# isolated_dcdc_5to3_3.net
KiCad netlist of a schematic drawn in Altium Designer
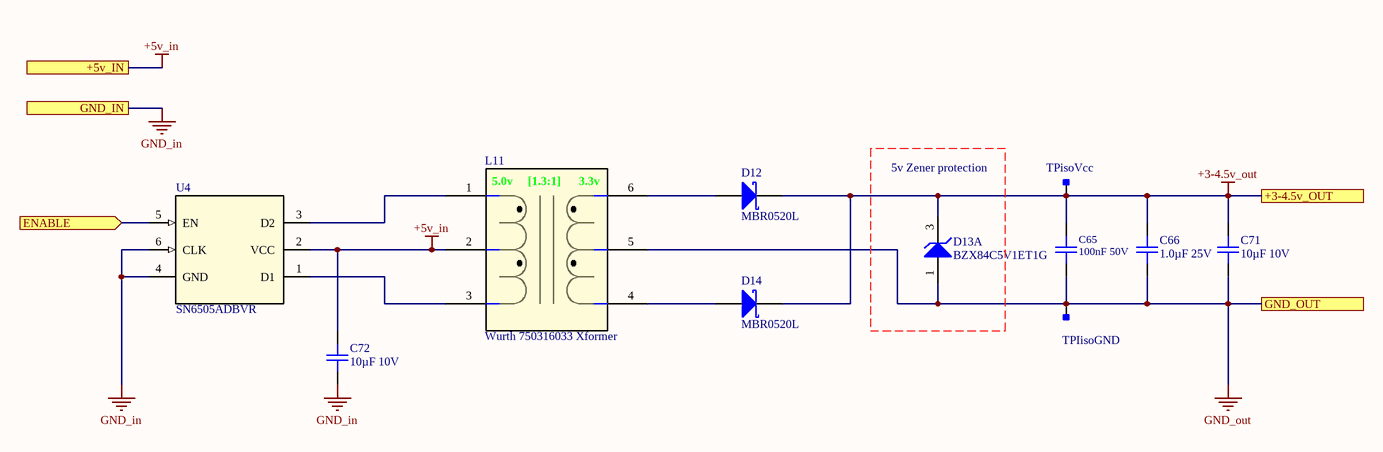
[diagram p0: isolated_dcdc_5to3.3.SchDoc]

(export (version "E")
  (design (tool "Eeschema 10.0.6"))
  (components
    (comp (ref "C65")
      (value "100nF 50V")
      (footprint "0603C")
      (description "Ceramic, 100nF, ±10%, 50V, X7R, –55 to 125°C, 0603 (1608),RoHS, Automotive")
      (fields (field (name "PART NUMBER") "GCJ188R71H104KA12") (field (name "TOLERANCE") "±10%"))
      (libsource (lib "master-010106") (part "gen_C_ceramic_100n_50V_X7R_0603"))
    )
    (comp (ref "C66")
      (value "1.0µF 25V")
      (footprint "0603C")
      (description "Ceramic, 1.0µF, ±10%, 25V, X7R, –55 to 125°C, 0603 (1608),RoHS, Automotive")
      (fields (field (name "PART NUMBER") "GCJ188R71E105KA01") (field (name "TOLERANCE") "±10%"))
      (libsource (lib "master-010106") (part "gen_C_ceramic_1u_25V_X7R_0603"))
    )
    (comp (ref "C71")
      (value "10µF 10V")
      (footprint "0805C")
      (description "Ceramic, 10µF, ±10%, 10V, X7R, –55 to 125°C, 0805 (2012),RoHS, Automotive")
      (fields (field (name "PART NUMBER") "GCJ21BR71A106KE01") (field (name "TOLERANCE") "±10%"))
      (libsource (lib "master-010106") (part "gen_C_ceramic_10u_10V_X7R_0805"))
    )
    (comp (ref "C72")
      (value "10µF 10V")
      (footprint "0805C")
      (description "Ceramic, 10µF, ±10%, 10V, X7R, –55 to 125°C, 0805 (2012),RoHS, Automotive")
      (fields (field (name "PART NUMBER") "GCJ21BR71A106KE01") (field (name "TOLERANCE") "±10%"))
      (libsource (lib "master-010106") (part "gen_C_ceramic_10u_10V_X7R_0805"))
    )
    (comp (ref "D12")
      (value "MBR0520L")
      (footprint "ONSC-SOD-123-2-425-04_V")
      (description "Schottky Diode, 20V, 0.2A, 2-pin SOD-123, RoHS, Tape and Reel")
      (fields (field (name "MANUFACTURER") "FairchildSemiconductor"))
      (libsource (lib "Altium Content Vault") (part "DSKY-KA-2"))
    )
    (comp (ref "D13")
      (value "BZX84C5V1ET1G")
      (footprint "ONSC-SOT-23-3-318-08_V")
      (description "Zener Voltage Regulator, 225 mW, 3-Pin SOT-23, Pb-Free, Tape and Reel")
      (fields (field (name "MANUFACTURER") "On Semiconductor"))
      (libsource (lib "Altium Content Vault") (part "ONSC-A1K3-3"))
    )
    (comp (ref "D14")
      (value "MBR0520L")
      (footprint "ONSC-SOD-123-2-425-04_V")
      (description "Schottky Diode, 20V, 0.2A, 2-pin SOD-123, RoHS, Tape and Reel")
      (fields (field (name "MANUFACTURER") "FairchildSemiconductor"))
      (libsource (lib "Altium Content Vault") (part "DSKY-KA-2"))
    )
    (comp (ref "L11")
      (value "Wurth 750316033 Xformer")
      (footprint "750316033")
      (description "Isolated interface power supply for CAN, RS-485, RS-422, RS-232, SPI, I2C, lower-power LAN")
      (fields
        (field (name "MANUFACTURER_PART_NUMBER") "50225C")
        (field (name "COPYRIGHT") "Copyright (C) 2018 Accelerated Designs. All rights reserved")
      )
      (libsource (lib "ti-import") (part "750316033"))
    )
    (comp (ref "TPIisoGND")
      (value "Testpoint_Square")
      (footprint "Testpoint_S1")
      (description "Testpoint, square")
      (libsource (lib "OE750") (part "Testpoint_Square"))
    )
    (comp (ref "TPisoVcc")
      (value "Testpoint_Square")
      (footprint "Testpoint_S1")
      (description "Testpoint, square")
      (libsource (lib "OE750") (part "Testpoint_Square"))
    )
    (comp (ref "U4")
      (value "SN6505ADBVR")
      (footprint "DBV0006A_N")
      (description "Imported")
      (fields
        (field (name "ALTERNATE_PARTNUMBER") "SN6505ADBVT")
        (field (name "MANUFACTURER") "Texas Instruments")
      )
      (libsource (lib "ti-import") (part "SN6505ADBVR"))
    )
  )
  (nets
    (net (code "1") (name "+3-4.5v_out") (class "Default")
      (node (ref "C65") (pin "2") (pinfunction "2_2") (pintype "passive"))
      (node (ref "C66") (pin "2") (pinfunction "2_2") (pintype "passive"))
      (node (ref "C71") (pin "2") (pinfunction "2_2") (pintype "passive"))
      (node (ref "D12") (pin "1") (pinfunction "K_1") (pintype "passive"))
      (node (ref "D13") (pin "3") (pinfunction "K_3") (pintype "passive"))
      (node (ref "D14") (pin "1") (pinfunction "K_1") (pintype "passive"))
      (node (ref "TPisoVcc") (pin "1") (pinfunction "1_1") (pintype "passive"))
    )
    (net (code "2") (name "+5v_in") (class "Default")
      (node (ref "C72") (pin "2") (pinfunction "2_2") (pintype "passive"))
      (node (ref "L11") (pin "2") (pinfunction "2_2") (pintype "passive"))
      (node (ref "U4") (pin "2") (pinfunction "VCC_2") (pintype "power_in"))
    )
    (net (code "3") (name "/ENABLE") (class "Default")
      (node (ref "U4") (pin "5") (pinfunction "EN_5") (pintype "input"))
    )
    (net (code "4") (name "GND_in") (class "Default")
      (node (ref "C72") (pin "1") (pinfunction "1_1") (pintype "passive"))
      (node (ref "U4") (pin "4") (pinfunction "GND_4") (pintype "power_in"))
      (node (ref "U4") (pin "6") (pinfunction "CLK_6") (pintype "input"))
    )
    (net (code "5") (name "GND_out") (class "Default")
      (node (ref "C65") (pin "1") (pinfunction "1_1") (pintype "passive"))
      (node (ref "C66") (pin "1") (pinfunction "1_1") (pintype "passive"))
      (node (ref "C71") (pin "1") (pinfunction "1_1") (pintype "passive"))
      (node (ref "D13") (pin "1") (pinfunction "A_1") (pintype "passive"))
      (node (ref "TPIisoGND") (pin "1") (pinfunction "1_1") (pintype "passive"))
    )
    (net (code "6") (name "Net-(U4-D1)") (class "Default")
      (node (ref "L11") (pin "3") (pinfunction "3_3") (pintype "passive"))
      (node (ref "U4") (pin "1") (pinfunction "D1_1") (pintype "open_collector"))
    )
    (net (code "7") (name "Net-(U4-D2)") (class "Default")
      (node (ref "L11") (pin "1") (pinfunction "1_1") (pintype "passive"))
      (node (ref "U4") (pin "3") (pinfunction "D2_3") (pintype "open_collector"))
    )
    (net (code "8") (name "unconnected-(D12-A-Pad2)") (class "Default")
      (node (ref "D12") (pin "2") (pinfunction "A_2") (pintype "passive"))
    )
    (net (code "9") (name "unconnected-(D14-A-Pad2)") (class "Default")
      (node (ref "D14") (pin "2") (pinfunction "A_2") (pintype "passive"))
    )
    (net (code "10") (name "unconnected-(L11-Pad4)") (class "Default")
      (node (ref "L11") (pin "4") (pinfunction "4_4") (pintype "passive"))
    )
    (net (code "11") (name "unconnected-(L11-Pad5)") (class "Default")
      (node (ref "L11") (pin "5") (pinfunction "5_5") (pintype "passive"))
    )
    (net (code "12") (name "unconnected-(L11-Pad6)") (class "Default")
      (node (ref "L11") (pin "6") (pinfunction "6_6") (pintype "passive"))
    )
  )
)
